# RPL_POWER_12V.net
KiCad netlist of a schematic drawn in Altium Designer
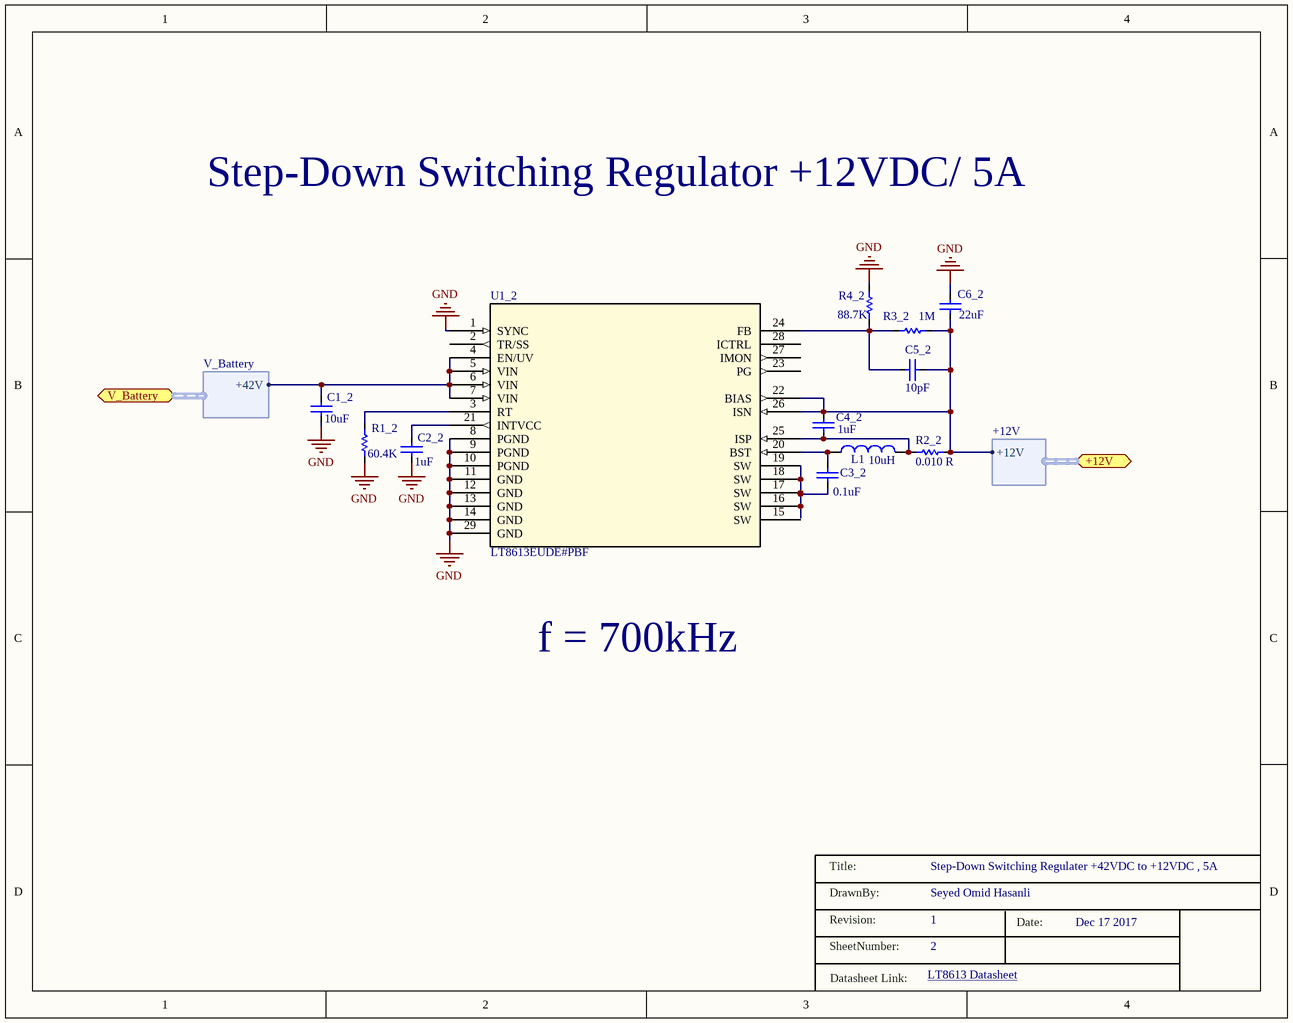
[diagram p0: RPL_POWER_12V.SchDoc]

(export (version "E")
  (design (tool "Eeschema 10.0.6"))
  (components
    (comp (ref "C1_2")
      (value "10uF")
      (footprint "C0805C475K9RACAUTO")
      (fields (field (name "Comment") "Cap"))
      (libsource (lib "Generic_Library") (part "Cap"))
    )
    (comp (ref "C2_2")
      (value "1uF")
      (footprint "C0805C475K9RACAUTO")
      (fields (field (name "Comment") "Cap"))
      (libsource (lib "Generic_Library") (part "Cap"))
    )
    (comp (ref "C3_2")
      (value "0.1uF")
      (footprint "C0805C475K9RACAUTO")
      (fields (field (name "Comment") "Cap"))
      (libsource (lib "Generic_Library") (part "Cap"))
    )
    (comp (ref "C4_2")
      (value "1uF")
      (footprint "C0805C475K9RACAUTO")
      (fields (field (name "Comment") "Cap"))
      (libsource (lib "Generic_Library") (part "Cap"))
    )
    (comp (ref "C5_2")
      (value "10pF")
      (footprint "C0805C475K9RACAUTO")
      (fields (field (name "Comment") "Cap"))
      (libsource (lib "Generic_Library") (part "Cap"))
    )
    (comp (ref "C6_2")
      (value "22uF")
      (footprint "C0805C475K9RACAUTO")
      (fields (field (name "Comment") "Cap"))
      (libsource (lib "Generic_Library") (part "Cap"))
    )
    (comp (ref "L1")
      (value "10uH")
      (footprint "XAL6060-103MEB")
      (fields (field (name "Comment") "COILCRAFT XAL6060"))
      (libsource (lib "Generic_Library") (part "Inductor"))
    )
    (comp (ref "R1_2")
      (value "60.4K")
      (footprint "SMD Resistors:RES 0805")
      (fields (field (name "Comment") "Res"))
      (libsource (lib "Generic_Library") (part "Res"))
    )
    (comp (ref "R2_2")
      (value "0.010 R")
      (footprint "SMD Resistors:RES 1206")
      (fields (field (name "Comment") "Res"))
      (libsource (lib "Generic_Library") (part "Res"))
    )
    (comp (ref "R3_2")
      (value "1M")
      (footprint "SMD Resistors:RES 0805")
      (fields (field (name "Comment") "Res"))
      (libsource (lib "Generic_Library") (part "Res"))
    )
    (comp (ref "R4_2")
      (value "88.7K")
      (footprint "SMD Resistors:RES 0805")
      (fields (field (name "Comment") "Res"))
      (libsource (lib "Generic_Library") (part "Res"))
    )
    (comp (ref "U1_2")
      (value "LT8613EUDE#PBF")
      (footprint "QFN-28_UDE-L")
      (description "Imported")
      (fields (field (name "MANUFACTURER_PART_NUMBER") "lt8613eude#pbf"))
      (libsource (lib "Generic_Library") (part "LT8613EUDE#PBF"))
    )
  )
  (nets
    (net (code "5") (name "GND") (class "Default")
      (node (ref "C1_2") (pin "1") (pinfunction "1_1") (pintype "passive"))
      (node (ref "C2_2") (pin "1") (pinfunction "1_1") (pintype "passive"))
      (node (ref "C6_2") (pin "2") (pinfunction "2_2") (pintype "passive"))
      (node (ref "R1_2") (pin "1") (pinfunction "1_1") (pintype "passive"))
      (node (ref "R4_2") (pin "2") (pinfunction "2_2") (pintype "passive"))
      (node (ref "U1_2") (pin "1") (pinfunction "SYNC_1") (pintype "input"))
      (node (ref "U1_2") (pin "10") (pinfunction "PGND_10") (pintype "power_in"))
      (node (ref "U1_2") (pin "11") (pinfunction "GND_11") (pintype "power_in"))
      (node (ref "U1_2") (pin "12") (pinfunction "GND_12") (pintype "power_in"))
      (node (ref "U1_2") (pin "13") (pinfunction "GND_13") (pintype "power_in"))
      (node (ref "U1_2") (pin "14") (pinfunction "GND_14") (pintype "power_in"))
      (node (ref "U1_2") (pin "29") (pinfunction "GND_29") (pintype "power_in"))
      (node (ref "U1_2") (pin "8") (pinfunction "PGND_8") (pintype "power_in"))
      (node (ref "U1_2") (pin "9") (pinfunction "PGND_9") (pintype "power_in"))
    )
    (net (code "6") (name "Net-(C3_2-Pad1)") (class "Default")
      (node (ref "C3_2") (pin "1") (pinfunction "1_1") (pintype "passive"))
      (node (ref "U1_2") (pin "16") (pinfunction "SW_16") (pintype "passive"))
      (node (ref "U1_2") (pin "17") (pinfunction "SW_17") (pintype "passive"))
      (node (ref "U1_2") (pin "18") (pinfunction "SW_18") (pintype "passive"))
      (node (ref "U1_2") (pin "19") (pinfunction "SW_19") (pintype "passive"))
    )
    (net (code "7") (name "Net-(U1_2-BIAS)") (class "Default")
      (node (ref "C4_2") (pin "1") (pinfunction "1_1") (pintype "passive"))
      (node (ref "C5_2") (pin "1") (pinfunction "1_1") (pintype "passive"))
      (node (ref "C6_2") (pin "1") (pinfunction "1_1") (pintype "passive"))
      (node (ref "R2_2") (pin "2") (pinfunction "2_2") (pintype "passive"))
      (node (ref "R3_2") (pin "2") (pinfunction "2_2") (pintype "passive"))
      (node (ref "U1_2") (pin "22") (pinfunction "BIAS_22") (pintype "output"))
      (node (ref "U1_2") (pin "26") (pinfunction "ISN_26") (pintype "input"))
    )
    (net (code "8") (name "Net-(U1_2-BST)") (class "Default")
      (node (ref "C3_2") (pin "2") (pinfunction "2_2") (pintype "passive"))
      (node (ref "L1") (pin "1") (pinfunction "1_1") (pintype "passive"))
      (node (ref "U1_2") (pin "20") (pinfunction "BST_20") (pintype "input"))
    )
    (net (code "9") (name "Net-(U1_2-EN{slash}UV)") (class "Default")
      (node (ref "C1_2") (pin "2") (pinfunction "2_2") (pintype "passive"))
      (node (ref "U1_2") (pin "4") (pinfunction "EN/UV_4") (pintype "passive"))
      (node (ref "U1_2") (pin "5") (pinfunction "VIN_5") (pintype "input"))
      (node (ref "U1_2") (pin "6") (pinfunction "VIN_6") (pintype "input"))
      (node (ref "U1_2") (pin "7") (pinfunction "VIN_7") (pintype "input"))
    )
    (net (code "10") (name "Net-(U1_2-FB)") (class "Default")
      (node (ref "C5_2") (pin "2") (pinfunction "2_2") (pintype "passive"))
      (node (ref "R3_2") (pin "1") (pinfunction "1_1") (pintype "passive"))
      (node (ref "R4_2") (pin "1") (pinfunction "1_1") (pintype "passive"))
      (node (ref "U1_2") (pin "24") (pinfunction "FB_24") (pintype "passive"))
    )
    (net (code "11") (name "Net-(U1_2-INTVCC)") (class "Default")
      (node (ref "C2_2") (pin "2") (pinfunction "2_2") (pintype "passive"))
      (node (ref "U1_2") (pin "21") (pinfunction "INTVCC_21") (pintype "output"))
    )
    (net (code "12") (name "Net-(U1_2-ISP)") (class "Default")
      (node (ref "C4_2") (pin "2") (pinfunction "2_2") (pintype "passive"))
      (node (ref "L1") (pin "2") (pinfunction "2_2") (pintype "passive"))
      (node (ref "R2_2") (pin "1") (pinfunction "1_1") (pintype "passive"))
      (node (ref "U1_2") (pin "25") (pinfunction "ISP_25") (pintype "input"))
    )
    (net (code "13") (name "Net-(U1_2-RT)") (class "Default")
      (node (ref "R1_2") (pin "2") (pinfunction "2_2") (pintype "passive"))
      (node (ref "U1_2") (pin "3") (pinfunction "RT_3") (pintype "passive"))
    )
    (net (code "14") (name "unconnected-(U1_2-ICTRL-Pad28)") (class "Default")
      (node (ref "U1_2") (pin "28") (pinfunction "ICTRL_28") (pintype "passive"))
    )
    (net (code "15") (name "unconnected-(U1_2-IMON-Pad27)") (class "Default")
      (node (ref "U1_2") (pin "27") (pinfunction "IMON_27") (pintype "output"))
    )
    (net (code "16") (name "unconnected-(U1_2-PG-Pad23)") (class "Default")
      (node (ref "U1_2") (pin "23") (pinfunction "PG_23") (pintype "output"))
    )
    (net (code "17") (name "unconnected-(U1_2-SW-Pad15)") (class "Default")
      (node (ref "U1_2") (pin "15") (pinfunction "SW_15") (pintype "passive"))
    )
    (net (code "18") (name "unconnected-(U1_2-TR{slash}SS-Pad2)") (class "Default")
      (node (ref "U1_2") (pin "2") (pinfunction "TR/SS_2") (pintype "output"))
    )
  )
)
